# SCH_10_28_2022_R3_HARWARE_TRAININGMODULE.net
KiCad netlist of a schematic drawn in EasyEDA
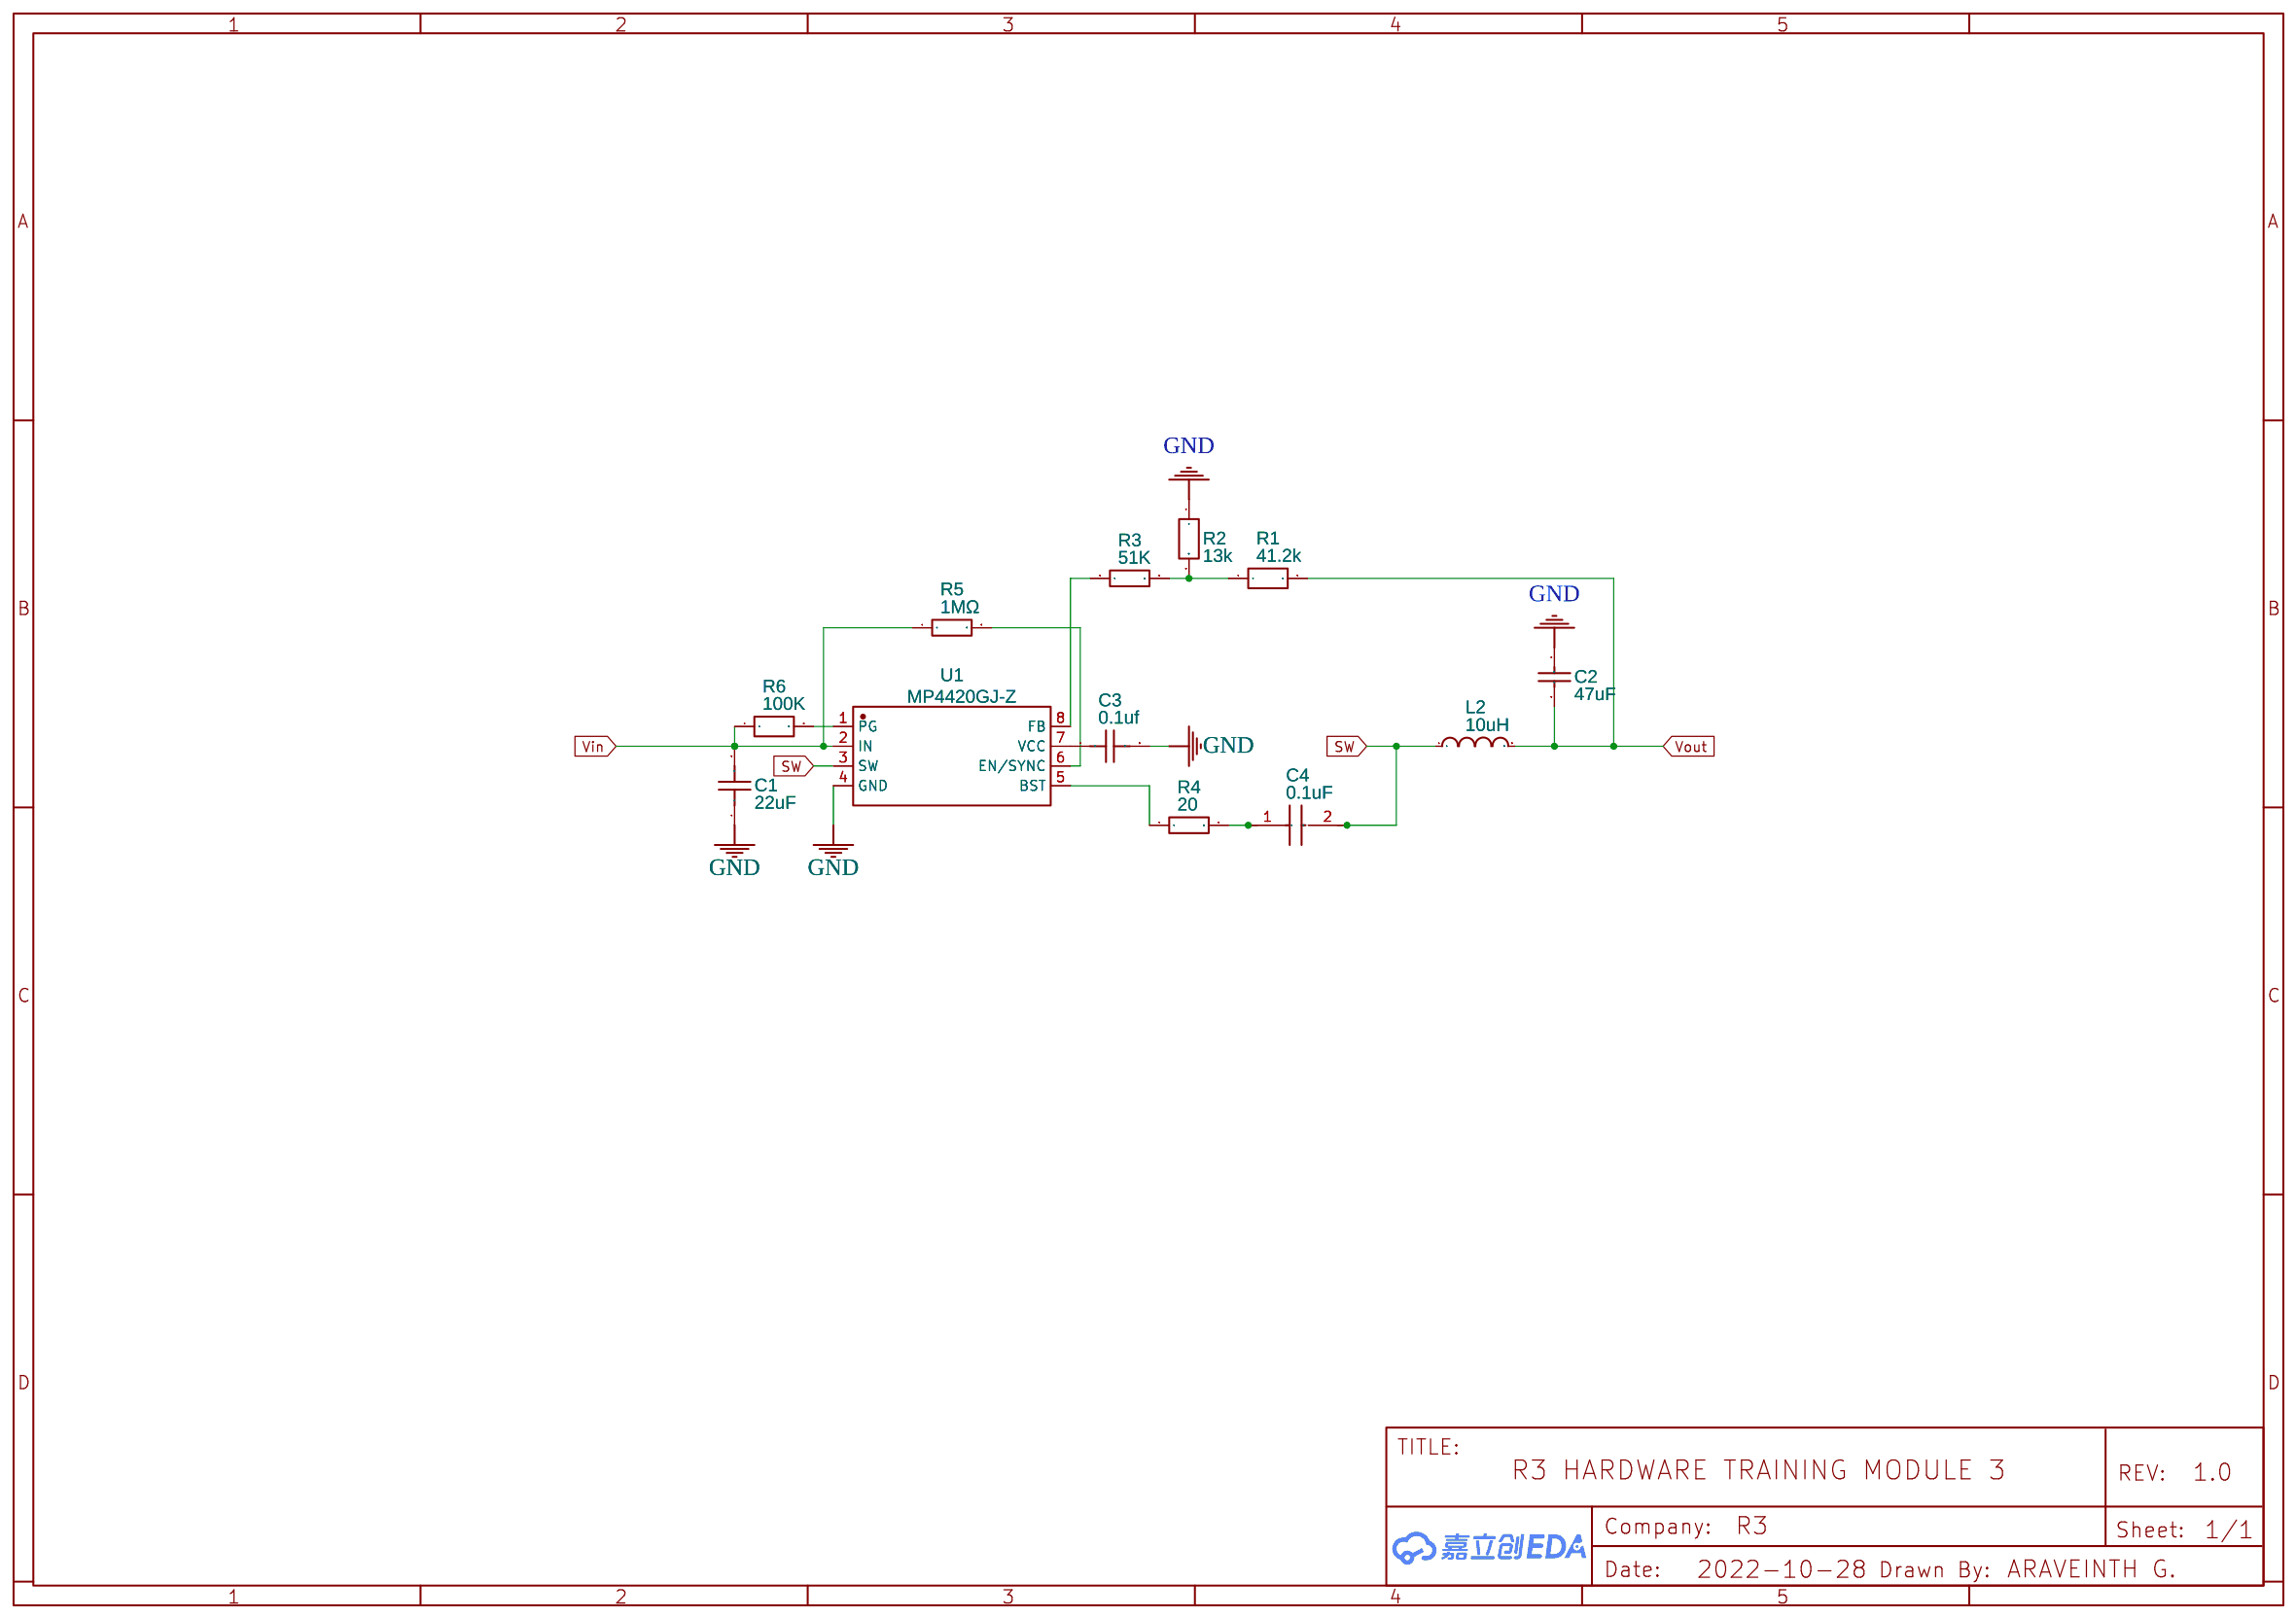
[diagram p0: schematic sheet]

(export (version "E")
  (design (tool "Eeschema 10.0.6"))
  (components
    (comp (ref "C1")
      (value "22uF")
      (fields
        (field (name "BOM_Manufacturer Part") "CL10A226MO7JZNC")
        (field (name "BOM_Supplier Part") "1276-7076-1-ND")
      )
      (libsource (lib "") (part "CL10A226MO7JZNC"))
    )
    (comp (ref "C2")
      (value "47uF")
      (fields
        (field (name "BOM_Manufacturer Part") "CL31A476MQHNNNE")
        (field (name "BOM_Supplier Part") "1276-1167-1-ND")
      )
      (libsource (lib "") (part "CL31A476MQHNNNE"))
    )
    (comp (ref "C3")
      (value "0.1uf")
      (fields
        (field (name "BOM_Manufacturer Part") "GRM033R6YA104KE14D")
        (field (name "BOM_Supplier Part") "490-10430-1-ND")
      )
      (libsource (lib "") (part "GRM033R6YA104KE14D"))
    )
    (comp (ref "C4")
      (value "0.1uF")
      (fields
        (field (name "BOM_Manufacturer Part") "CAP CER 0.1UF 6.3V X5R 0201")
        (field (name "BOM_Supplier Part") "478-5266-1-ND")
      )
      (libsource (lib "") (part "02016D104KAT2A"))
    )
    (comp (ref "L2")
      (value "10uH")
      (fields
        (field (name "BOM_Manufacturer Part") "B82559A7103A025")
        (field (name "BOM_Supplier Part") "C1329446")
      )
      (libsource (lib "") (part "B82559A7103A025"))
    )
    (comp (ref "R1")
      (value "41.2k")
      (fields
        (field (name "BOM_Manufacturer Part") "RC1206FR-0741K2L")
        (field (name "BOM_Supplier Part") "311-41.2KFRCT-ND")
      )
      (libsource (lib "") (part "RC1206FR-0741K2L"))
    )
    (comp (ref "R2")
      (value "13k")
      (fields
        (field (name "BOM_Manufacturer Part") "RC1206FR-0713KL")
        (field (name "BOM_Supplier Part") "311-13.0KFRCT-ND")
      )
      (libsource (lib "") (part "RC1206FR-0713KL"))
    )
    (comp (ref "R3")
      (value "51K")
      (fields
        (field (name "BOM_Manufacturer Part") "RC1206JR-0751KL")
        (field (name "BOM_Supplier Part") "311-51KERCT-ND")
      )
      (libsource (lib "") (part "RC1206JR-0751KL"))
    )
    (comp (ref "R4")
      (value "20")
      (fields
        (field (name "BOM_Manufacturer Part") "RC1206JR-0720RL")
        (field (name "BOM_Supplier Part") "311-20ERCT-ND")
      )
      (libsource (lib "") (part "RC1206JR-0720RL"))
    )
    (comp (ref "R5")
      (value "1MΩ")
      (fields
        (field (name "BOM_Manufacturer Part") "RMCF1206JT1M00")
        (field (name "BOM_Supplier Part") "RMCF1206JT1M00CT-ND")
      )
      (libsource (lib "") (part "RMCF1206JT1M00"))
    )
    (comp (ref "R6")
      (value "100K")
      (fields
        (field (name "BOM_Manufacturer Part") "AC1206JR-07100KL")
        (field (name "BOM_Supplier Part") "YAG3912CT-ND")
      )
      (libsource (lib "") (part "AC1206JR-07100KL"))
    )
    (comp (ref "U1")
      (value "MP4420GJ-Z")
      (fields (field (name "BOM_Supplier Part") "1589-MP4420GJ-ZCT-ND"))
      (libsource (lib "") (part "MP4420GJ-P"))
    )
  )
  (nets
    (net (code "1") (name "GND") (class "Default")
      (node (ref "C1") (pin "1") (pinfunction "1_1") (pintype "unspecified"))
      (node (ref "C2") (pin "1") (pinfunction "1_1") (pintype "input"))
      (node (ref "C3") (pin "2") (pinfunction "2_2") (pintype "unspecified"))
      (node (ref "R2") (pin "1") (pinfunction "1_1") (pintype "unspecified"))
      (node (ref "U1") (pin "4") (pinfunction "GND_4") (pintype "unspecified"))
    )
    (net (code "2") (name "Net-(C4-Pad1)") (class "Default")
      (node (ref "C4") (pin "1") (pinfunction "1_1") (pintype "bidirectional"))
      (node (ref "R4") (pin "2") (pinfunction "2_2") (pintype "input"))
    )
    (net (code "3") (name "Net-(R1-Pad1)") (class "Default")
      (node (ref "R1") (pin "1") (pinfunction "1_1") (pintype "unspecified"))
      (node (ref "R2") (pin "2") (pinfunction "2_2") (pintype "unspecified"))
      (node (ref "R3") (pin "2") (pinfunction "2_2") (pintype "input"))
    )
    (net (code "4") (name "Net-(U1-BST)") (class "Default")
      (node (ref "R4") (pin "1") (pinfunction "1_1") (pintype "input"))
      (node (ref "U1") (pin "5") (pinfunction "BST_5") (pintype "unspecified"))
    )
    (net (code "5") (name "Net-(U1-EN{slash}SYNC)") (class "Default")
      (node (ref "R5") (pin "2") (pinfunction "2_2") (pintype "unspecified"))
      (node (ref "U1") (pin "6") (pinfunction "EN/SYNC_6") (pintype "unspecified"))
    )
    (net (code "6") (name "Net-(U1-FB)") (class "Default")
      (node (ref "R3") (pin "1") (pinfunction "1_1") (pintype "input"))
      (node (ref "U1") (pin "8") (pinfunction "FB_8") (pintype "unspecified"))
    )
    (net (code "7") (name "Net-(U1-PG)") (class "Default")
      (node (ref "R6") (pin "2") (pinfunction "2_2") (pintype "unspecified"))
      (node (ref "U1") (pin "1") (pinfunction "PG_1") (pintype "unspecified"))
    )
    (net (code "8") (name "Net-(U1-VCC)") (class "Default")
      (node (ref "C3") (pin "1") (pinfunction "1_1") (pintype "unspecified"))
      (node (ref "U1") (pin "7") (pinfunction "VCC_7") (pintype "unspecified"))
    )
    (net (code "9") (name "SW") (class "Default")
      (node (ref "C4") (pin "2") (pinfunction "2_2") (pintype "bidirectional"))
      (node (ref "L2") (pin "1") (pinfunction "1_1") (pintype "unspecified"))
      (node (ref "U1") (pin "3") (pinfunction "SW_3") (pintype "unspecified"))
    )
    (net (code "10") (name "Vin") (class "Default")
      (node (ref "C1") (pin "2") (pinfunction "2_2") (pintype "unspecified"))
      (node (ref "R5") (pin "1") (pinfunction "1_1") (pintype "unspecified"))
      (node (ref "R6") (pin "1") (pinfunction "1_1") (pintype "unspecified"))
      (node (ref "U1") (pin "2") (pinfunction "IN_2") (pintype "unspecified"))
    )
    (net (code "11") (name "Vout") (class "Default")
      (node (ref "C2") (pin "2") (pinfunction "2_2") (pintype "input"))
      (node (ref "L2") (pin "2") (pinfunction "2_2") (pintype "unspecified"))
      (node (ref "R1") (pin "2") (pinfunction "2_2") (pintype "unspecified"))
    )
  )
)
